# BH1750.net
KiCad netlist of a schematic drawn in Altium Designer
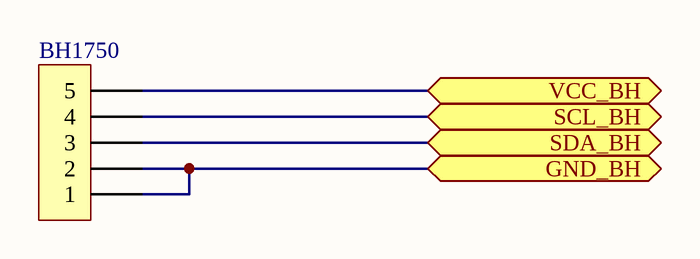
[diagram p0: BH1750.SchDoc]

(export (version "E")
  (design (tool "Eeschema 10.0.6"))
  (components
    (comp (ref "BH1750")
      (value "Header 5P 2.54 Duc Thang")
      (footprint "XH2.54M-5")
      (description "Cắm")
      (libsource (lib "Altium_Lib_by_KhueNguyenCreator") (part "Header 5P 2.54 Duc Thang"))
    )
  )
  (nets
    (net (code "1") (name "/GND_BH") (class "Default")
      (node (ref "BH1750") (pin "1") (pinfunction "1_1") (pintype "passive"))
      (node (ref "BH1750") (pin "2") (pinfunction "2_2") (pintype "passive"))
    )
    (net (code "2") (name "/SCL_BH") (class "Default")
      (node (ref "BH1750") (pin "4") (pinfunction "4_4") (pintype "passive"))
    )
    (net (code "3") (name "/SDA_BH") (class "Default")
      (node (ref "BH1750") (pin "3") (pinfunction "3_3") (pintype "passive"))
    )
    (net (code "4") (name "/VCC_BH") (class "Default")
      (node (ref "BH1750") (pin "5") (pinfunction "5_5") (pintype "passive"))
    )
  )
)
